# Netscale48HD_RFID_Reader_Writer.net
KiCad netlist of a schematic drawn in Altium Designer
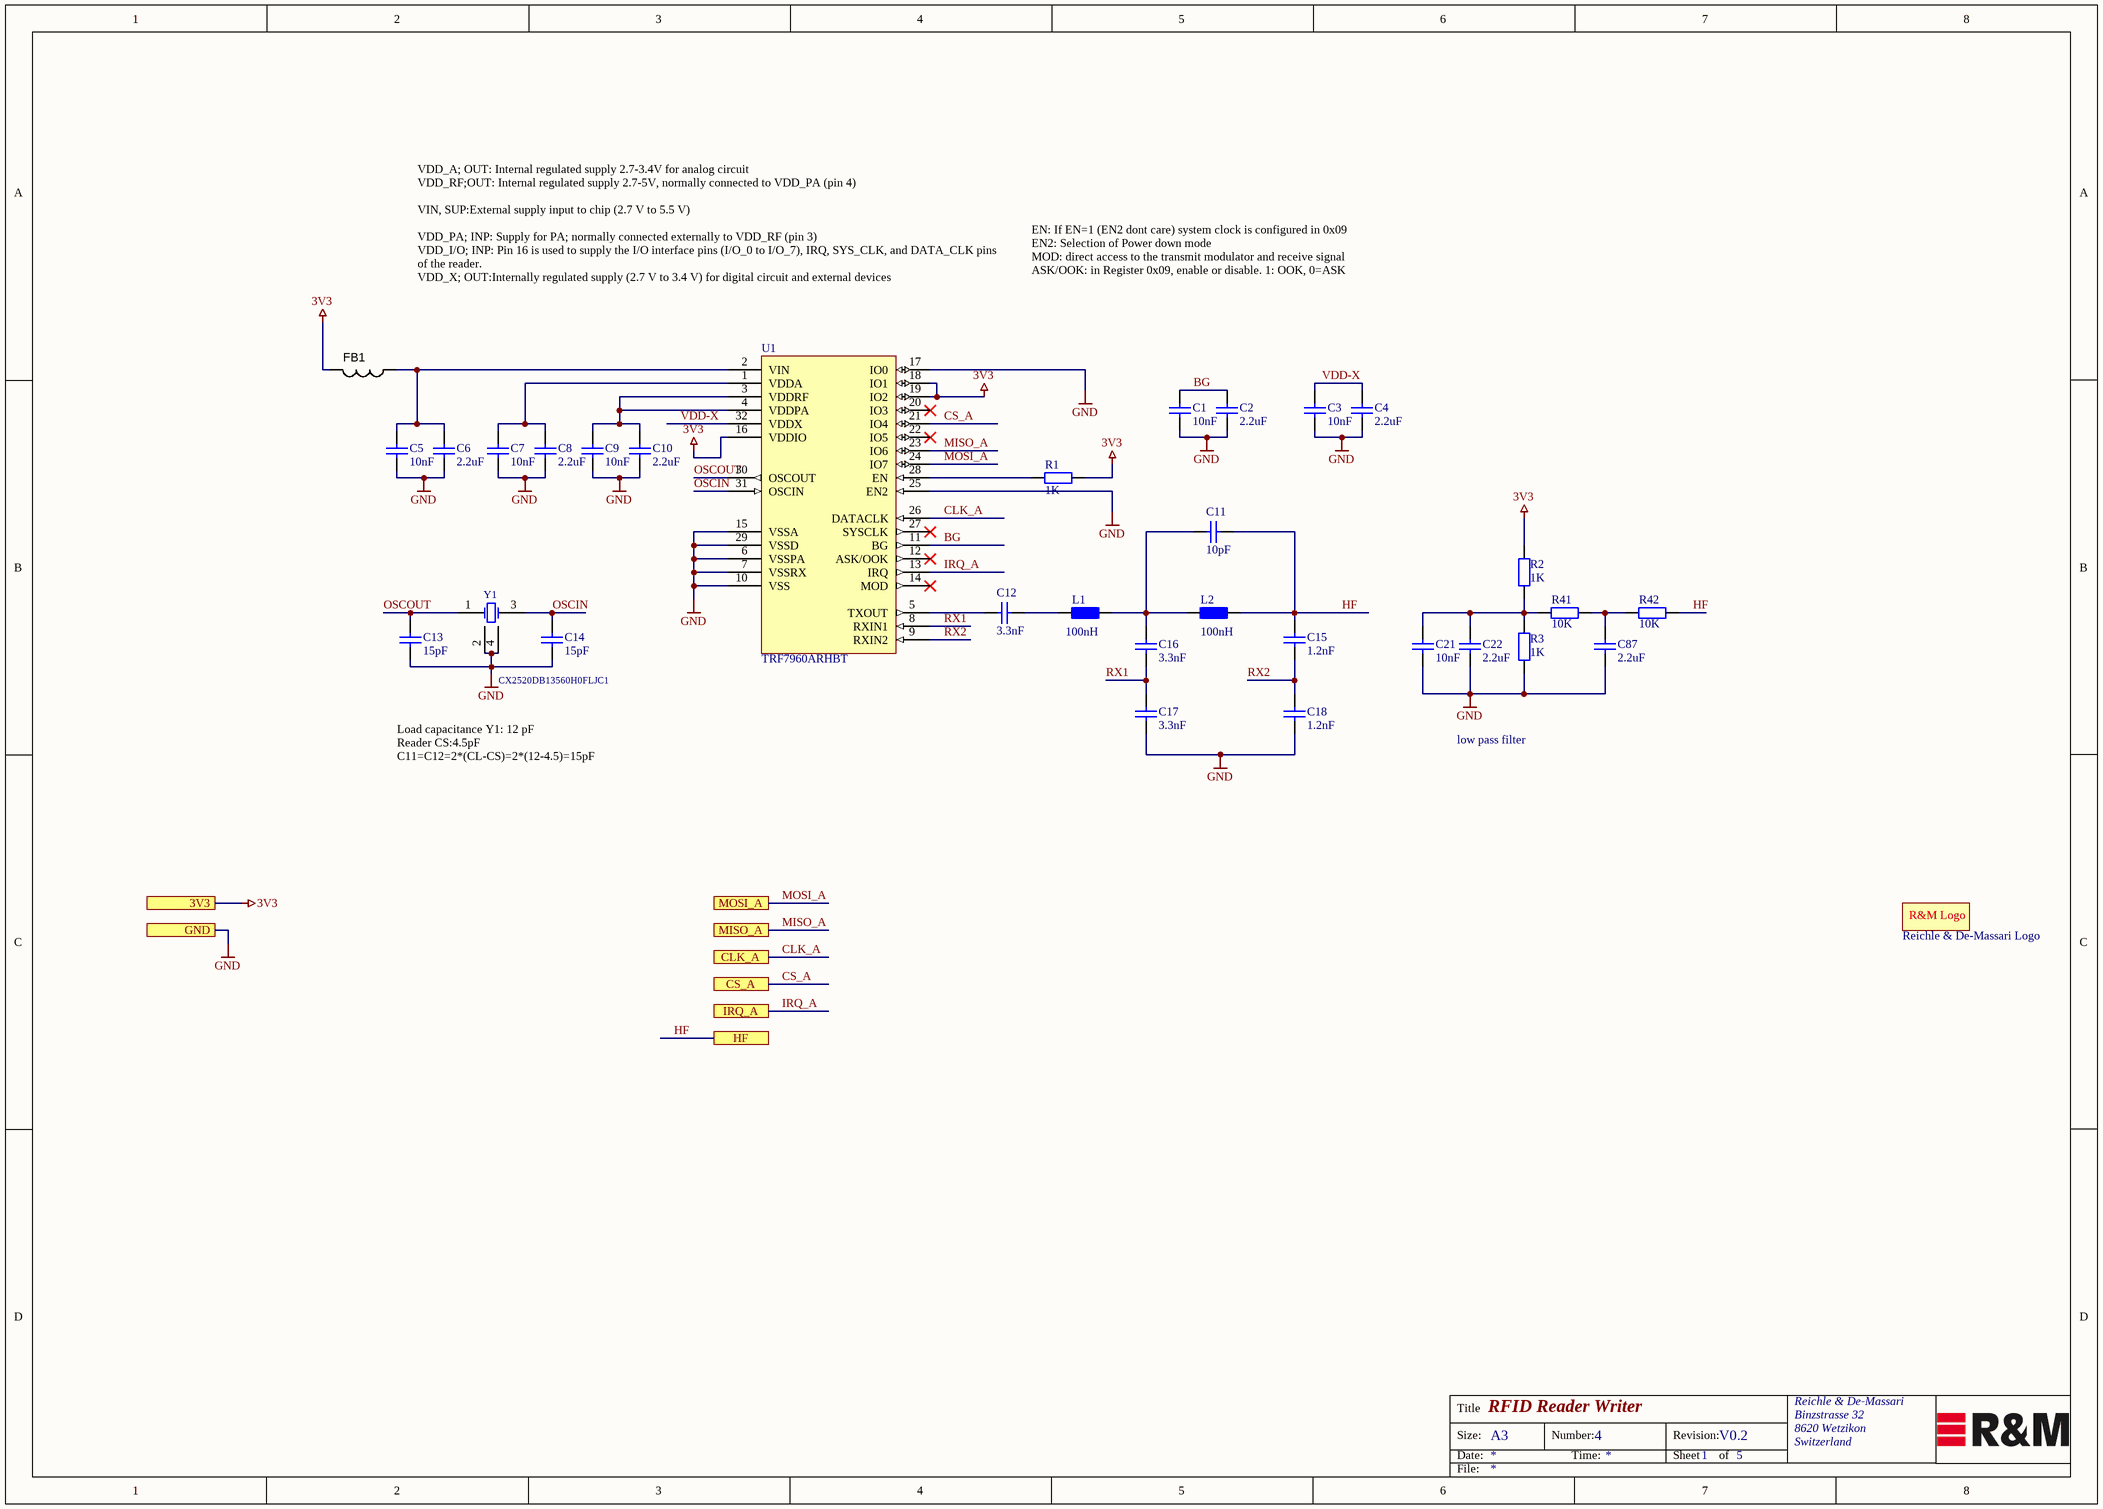
[diagram p0: Netscale48HD_RFID_Reader_Writer.SchDoc]

(export (version "E")
  (design (tool "Eeschema 10.0.6"))
  (components
    (comp (ref "*1")
      (value "Reichle & De-Massari Logo")
      (footprint "SYMBOL_R&M")
      (libsource (lib "RDM_ALT_SCH") (part "SYMBOL_R&M"))
    )
    (comp (ref "C1")
      (value "10nF")
      (footprint "Ceramic Capacitor 0402 EIA")
      (description "10000pF ±10% 50V Keramikkondensatoren X7R 0402 (1005 metrisch) CL05B103KB5NNNC")
      (fields (field (name "TOLERANCE") "±10%") (field (name "VOLTAGE") "50V"))
      (libsource (lib "RDM_ALT_SCH") (part "Cap_10nF_0402"))
    )
    (comp (ref "C2")
      (value "2.2uF")
      (footprint "Ceramic Capacitor 0402 EIA")
      (description "Multilayer Ceramic Capacitors MLCC - SMD/SMT 0402 2.2uF 6.3volts *Derate Voltage/Temp")
      (fields (field (name "TOLERANCE") "±20%") (field (name "VOLTAGE") "6.3V"))
      (libsource (lib "RDM_ALT_SCH") (part "Cap_2.2uF_0402_6.3V"))
    )
    (comp (ref "C3")
      (value "10nF")
      (footprint "Ceramic Capacitor 0402 EIA")
      (description "10000pF ±10% 50V Keramikkondensatoren X7R 0402 (1005 metrisch) CL05B103KB5NNNC")
      (fields (field (name "TOLERANCE") "±10%") (field (name "VOLTAGE") "50V"))
      (libsource (lib "RDM_ALT_SCH") (part "Cap_10nF_0402"))
    )
    (comp (ref "C4")
      (value "2.2uF")
      (footprint "Ceramic Capacitor 0402 EIA")
      (description "Multilayer Ceramic Capacitors MLCC - SMD/SMT 0402 2.2uF 6.3volts *Derate Voltage/Temp")
      (fields (field (name "TOLERANCE") "±20%") (field (name "VOLTAGE") "6.3V"))
      (libsource (lib "RDM_ALT_SCH") (part "Cap_2.2uF_0402_6.3V"))
    )
    (comp (ref "C5")
      (value "10nF")
      (footprint "Ceramic Capacitor 0402 EIA")
      (description "10000pF ±10% 50V Keramikkondensatoren X7R 0402 (1005 metrisch) CL05B103KB5NNNC")
      (fields (field (name "TOLERANCE") "±10%") (field (name "VOLTAGE") "50V"))
      (libsource (lib "RDM_ALT_SCH") (part "Cap_10nF_0402"))
    )
    (comp (ref "C6")
      (value "2.2uF")
      (footprint "Ceramic Capacitor 0402 EIA")
      (description "Multilayer Ceramic Capacitors MLCC - SMD/SMT 0402 2.2uF 6.3volts *Derate Voltage/Temp")
      (fields (field (name "TOLERANCE") "±20%") (field (name "VOLTAGE") "6.3V"))
      (libsource (lib "RDM_ALT_SCH") (part "Cap_2.2uF_0402_6.3V"))
    )
    (comp (ref "C7")
      (value "10nF")
      (footprint "Ceramic Capacitor 0402 EIA")
      (description "10000pF ±10% 50V Keramikkondensatoren X7R 0402 (1005 metrisch) CL05B103KB5NNNC")
      (fields (field (name "TOLERANCE") "±10%") (field (name "VOLTAGE") "50V"))
      (libsource (lib "RDM_ALT_SCH") (part "Cap_10nF_0402"))
    )
    (comp (ref "C8")
      (value "2.2uF")
      (footprint "Ceramic Capacitor 0402 EIA")
      (description "Multilayer Ceramic Capacitors MLCC - SMD/SMT 0402 2.2uF 6.3volts *Derate Voltage/Temp")
      (fields (field (name "TOLERANCE") "±20%") (field (name "VOLTAGE") "6.3V"))
      (libsource (lib "RDM_ALT_SCH") (part "Cap_2.2uF_0402_6.3V"))
    )
    (comp (ref "C9")
      (value "10nF")
      (footprint "Ceramic Capacitor 0402 EIA")
      (description "10000pF ±10% 50V Keramikkondensatoren X7R 0402 (1005 metrisch) CL05B103KB5NNNC")
      (fields (field (name "TOLERANCE") "±10%") (field (name "VOLTAGE") "50V"))
      (libsource (lib "RDM_ALT_SCH") (part "Cap_10nF_0402"))
    )
    (comp (ref "C10")
      (value "2.2uF")
      (footprint "Ceramic Capacitor 0402 EIA")
      (description "Multilayer Ceramic Capacitors MLCC - SMD/SMT 0402 2.2uF 6.3volts *Derate Voltage/Temp")
      (fields (field (name "TOLERANCE") "±20%") (field (name "VOLTAGE") "6.3V"))
      (libsource (lib "RDM_ALT_SCH") (part "Cap_2.2uF_0402_6.3V"))
    )
    (comp (ref "C11")
      (value "10pF")
      (footprint "Ceramic Capacitor 0402 EIA")
      (description "Multilayer Ceramic Capacitors MLCC - SMD/SMT 0402 10pF 50Volts C0G 1%")
      (fields (field (name "TOLERANCE") "1%") (field (name "VOLTAGE") "50VDC"))
      (libsource (lib "RDM_ALT_SCH") (part "Cap_10pF_0402"))
    )
    (comp (ref "C12")
      (value "3.3nF")
      (footprint "Ceramic Capacitor 0402 EIA")
      (description "Multilayer Ceramic Capacitors MLCC - SMD/SMT 0402 3300pF 50volts X7R 5%")
      (fields (field (name "TOLERANCE") "5%") (field (name "VOLTAGE") "50VDC"))
      (libsource (lib "RDM_ALT_SCH") (part "Cap_3.3nF_0402"))
    )
    (comp (ref "C13")
      (value "15pF")
      (footprint "Ceramic Capacitor 0402 EIA")
      (description "Multilayer Ceramic Capacitors MLCC - SMD/SMT 0402 15pF 50Volts C0G 5%")
      (fields (field (name "TOLERANCE") "±5%") (field (name "VOLTAGE") "50V"))
      (libsource (lib "RDM_ALT_SCH") (part "Cap_15pF_0402"))
    )
    (comp (ref "C14")
      (value "15pF")
      (footprint "Ceramic Capacitor 0402 EIA")
      (description "Multilayer Ceramic Capacitors MLCC - SMD/SMT 0402 15pF 50Volts C0G 5%")
      (fields (field (name "TOLERANCE") "±5%") (field (name "VOLTAGE") "50V"))
      (libsource (lib "RDM_ALT_SCH") (part "Cap_15pF_0402"))
    )
    (comp (ref "C15")
      (value "1.2nF")
      (footprint "Ceramic Capacitor 0402 EIA")
      (description "Multilayer Ceramic Capacitors MLCC - SMD/SMT 50V 1200pF C0G 0402 5%")
      (fields (field (name "TOLERANCE") "5%") (field (name "VOLTAGE") "50VDC"))
      (libsource (lib "RDM_ALT_SCH") (part "Cap_1.2nF_0402"))
    )
    (comp (ref "C16")
      (value "3.3nF")
      (footprint "Ceramic Capacitor 0402 EIA")
      (description "Multilayer Ceramic Capacitors MLCC - SMD/SMT 0402 3300pF 50volts X7R 5%")
      (fields (field (name "TOLERANCE") "5%") (field (name "VOLTAGE") "50VDC"))
      (libsource (lib "RDM_ALT_SCH") (part "Cap_3.3nF_0402"))
    )
    (comp (ref "C17")
      (value "3.3nF")
      (footprint "Ceramic Capacitor 0402 EIA")
      (description "Multilayer Ceramic Capacitors MLCC - SMD/SMT 0402 3300pF 50volts X7R 5%")
      (fields (field (name "TOLERANCE") "5%") (field (name "VOLTAGE") "50VDC"))
      (libsource (lib "RDM_ALT_SCH") (part "Cap_3.3nF_0402"))
    )
    (comp (ref "C18")
      (value "1.2nF")
      (footprint "Ceramic Capacitor 0402 EIA")
      (description "Multilayer Ceramic Capacitors MLCC - SMD/SMT 50V 1200pF C0G 0402 5%")
      (fields (field (name "TOLERANCE") "5%") (field (name "VOLTAGE") "50VDC"))
      (libsource (lib "RDM_ALT_SCH") (part "Cap_1.2nF_0402"))
    )
    (comp (ref "C21")
      (value "10nF")
      (footprint "Ceramic Capacitor 0402 EIA")
      (description "10000pF ±10% 50V Keramikkondensatoren X7R 0402 (1005 metrisch) CL05B103KB5NNNC")
      (fields (field (name "TOLERANCE") "±10%") (field (name "VOLTAGE") "50V"))
      (libsource (lib "RDM_ALT_SCH") (part "Cap_10nF_0402"))
    )
    (comp (ref "C22")
      (value "2.2uF")
      (footprint "Ceramic Capacitor 0402 EIA")
      (description "Multilayer Ceramic Capacitors MLCC - SMD/SMT 0402 2.2uF 6.3volts *Derate Voltage/Temp")
      (fields (field (name "TOLERANCE") "±20%") (field (name "VOLTAGE") "6.3V"))
      (libsource (lib "RDM_ALT_SCH") (part "Cap_2.2uF_0402_6.3V"))
    )
    (comp (ref "C87")
      (value "2.2uF")
      (footprint "Ceramic Capacitor 0402 EIA")
      (description "Multilayer Ceramic Capacitors MLCC - SMD/SMT 0402 2.2uF 6.3volts *Derate Voltage/Temp")
      (fields (field (name "TOLERANCE") "±20%") (field (name "VOLTAGE") "6.3V"))
      (libsource (lib "RDM_ALT_SCH") (part "Cap_2.2uF_0402_6.3V"))
    )
    (comp (ref "FB1")
      (value "BK1005HS102-T")
      (footprint "CAPC1005X55N")
      (description "FERRITE BEAD 1 KOHM 0402 1LN")
      (fields (field (name "MANUFACTURER") "Taiyo Yuden"))
      (libsource (lib "PBL - Inductors") (part "FERRITE_2K2-100MHz_0603"))
    )
    (comp (ref "L1")
      (value "100nH")
      (footprint "Inductor 0603 EIA")
      (description "100nH Unshielded Multilayer Inductor 300mA 100 mOhm Max 0603 (1608 Metric)")
      (fields (field (name "MANUFACTURER") "Taiyo Yuden") (field (name "Comment") "HK1608R10J-T"))
      (libsource (lib "altium-import") (part "root_0_706xx_R+M_InteliPhyII_KTI-00029-A.1_"))
    )
    (comp (ref "L2")
      (value "100nH")
      (footprint "Inductor 0603 EIA")
      (description "100nH Unshielded Multilayer Inductor 300mA 100 mOhm Max 0603 (1608 Metric)")
      (fields (field (name "MANUFACTURER") "Taiyo Yuden") (field (name "Comment") "HK1608R10J-T"))
      (libsource (lib "altium-import") (part "root_0_706xx_R+M_InteliPhyII_KTI-00029-A.1_"))
    )
    (comp (ref "R1")
      (value "1K")
      (footprint "RESC1005X40N")
      (description "RES SMD 1K OHM 1% 1/16W 0402")
      (fields (field (name "MANUFACTURER") "Yageo") (field (name "Comment") "RC0402FR-071KL"))
      (libsource (lib "RDM_Altium_Library") (part "PassResBas0201-00654-A.2"))
    )
    (comp (ref "R2")
      (value "1K")
      (footprint "RESC1005X40N")
      (description "RES SMD 1K OHM 1% 1/16W 0402")
      (fields (field (name "MANUFACTURER") "Yageo") (field (name "Comment") "RC0402FR-071KL"))
      (libsource (lib "NTB Vault") (part "PassResBas0201-00654-A.2"))
    )
    (comp (ref "R3")
      (value "1K")
      (footprint "RESC1005X40N")
      (description "RES SMD 1K OHM 1% 1/16W 0402")
      (fields (field (name "MANUFACTURER") "Yageo") (field (name "Comment") "RC0402FR-071KL"))
      (libsource (lib "NTB Vault") (part "PassResBas0201-00654-A.2"))
    )
    (comp (ref "R41")
      (value "10K")
      (footprint "Resistor 0402 EIA")
      (description "SMD 10K ohm 1% 50V General Purpose")
      (fields (field (name "TOLERANCE") "1%") (field (name "POWER") "63mW"))
      (libsource (lib "RDM_ALT_SCH") (part "Res_10K_0402"))
    )
    (comp (ref "R42")
      (value "10K")
      (footprint "Resistor 0402 EIA")
      (description "SMD 10K ohm 1% 50V General Purpose")
      (fields (field (name "TOLERANCE") "1%") (field (name "POWER") "63mW"))
      (libsource (lib "RDM_ALT_SCH") (part "Res_10K_0402"))
    )
    (comp (ref "U1")
      (value "TRF7960ARHBT")
      (footprint "TexasInstruments_32-VFQFN_32_R")
      (fields (field (name "MANUFACTURER") "Texas Instruments"))
      (libsource (lib "RDM_Altium_Library") (part "TexasInstruments_TRF7960ARHBT_32-VFQFN_32"))
    )
    (comp (ref "Y1")
      (value "CX2520DB13560H0FLJC1")
      (footprint "AVX/Kyocera_DFN4_4_RWH")
      (description "13.56MHz ±10ppm Crystal 12pF 150 Ohms 4-SMD, No Lead")
      (fields (field (name "MANUFACTURER") "Kyocera International Inc. Electronic Components"))
      (libsource (lib "RDM_Altium_Library") (part "CRYSTAL_4Pin_1_3_1"))
    )
  )
  (nets
    (net (code "1") (name "/BG") (class "Default")
      (node (ref "C1") (pin "2") (pinfunction "2_2") (pintype "passive"))
      (node (ref "C2") (pin "2") (pinfunction "2_2") (pintype "passive"))
      (node (ref "U1") (pin "11") (pinfunction "BG_11") (pintype "output"))
    )
    (net (code "2") (name "/CLK_A") (class "Default")
      (node (ref "U1") (pin "26") (pinfunction "DATACLK_26") (pintype "input"))
    )
    (net (code "3") (name "/CS_A") (class "Default")
      (node (ref "U1") (pin "21") (pinfunction "IO4_21") (pintype "bidirectional"))
    )
    (net (code "4") (name "/HF") (class "Default")
      (node (ref "C11") (pin "1") (pinfunction "1_1") (pintype "passive"))
      (node (ref "C15") (pin "2") (pinfunction "2_2") (pintype "passive"))
      (node (ref "L2") (pin "2") (pinfunction "2_2") (pintype "passive"))
      (node (ref "R42") (pin "2") (pinfunction "2_2") (pintype "passive"))
    )
    (net (code "5") (name "/IRQ_A") (class "Default")
      (node (ref "U1") (pin "13") (pinfunction "IRQ_13") (pintype "output"))
    )
    (net (code "6") (name "/MISO_A") (class "Default")
      (node (ref "U1") (pin "23") (pinfunction "IO6_23") (pintype "bidirectional"))
    )
    (net (code "7") (name "/MOSI_A") (class "Default")
      (node (ref "U1") (pin "24") (pinfunction "IO7_24") (pintype "bidirectional"))
    )
    (net (code "8") (name "/OSCIN") (class "Default")
      (node (ref "C14") (pin "2") (pinfunction "2_2") (pintype "passive"))
      (node (ref "U1") (pin "31") (pinfunction "OSCIN_31") (pintype "input"))
      (node (ref "Y1") (pin "3") (pinfunction "OSC2_3") (pintype "passive"))
    )
    (net (code "9") (name "/OSCOUT") (class "Default")
      (node (ref "C13") (pin "2") (pinfunction "2_2") (pintype "passive"))
      (node (ref "U1") (pin "30") (pinfunction "OSCOUT_30") (pintype "output"))
      (node (ref "Y1") (pin "1") (pinfunction "OSC1_1") (pintype "passive"))
    )
    (net (code "10") (name "/RX1") (class "Default")
      (node (ref "C16") (pin "1") (pinfunction "1_1") (pintype "passive"))
      (node (ref "C17") (pin "2") (pinfunction "2_2") (pintype "passive"))
      (node (ref "U1") (pin "8") (pinfunction "RXIN1_8") (pintype "input"))
    )
    (net (code "11") (name "/RX2") (class "Default")
      (node (ref "C15") (pin "1") (pinfunction "1_1") (pintype "passive"))
      (node (ref "C18") (pin "2") (pinfunction "2_2") (pintype "passive"))
      (node (ref "U1") (pin "9") (pinfunction "RXIN2_9") (pintype "input"))
    )
    (net (code "12") (name "/VDD-X") (class "Default")
      (node (ref "C3") (pin "2") (pinfunction "2_2") (pintype "passive"))
      (node (ref "C4") (pin "2") (pinfunction "2_2") (pintype "passive"))
      (node (ref "U1") (pin "32") (pinfunction "VDDX_32") (pintype "power_in"))
    )
    (net (code "13") (name "3V3") (class "Default")
      (node (ref "FB1") (pin "2") (pinfunction "2_2") (pintype "passive"))
      (node (ref "R1") (pin "1") (pinfunction "1_1") (pintype "passive"))
      (node (ref "R2") (pin "1") (pinfunction "1_1") (pintype "passive"))
      (node (ref "U1") (pin "16") (pinfunction "VDDIO_16") (pintype "power_in"))
      (node (ref "U1") (pin "18") (pinfunction "IO1_18") (pintype "bidirectional"))
      (node (ref "U1") (pin "19") (pinfunction "IO2_19") (pintype "bidirectional"))
    )
    (net (code "14") (name "GND") (class "Default")
      (node (ref "C1") (pin "1") (pinfunction "1_1") (pintype "passive"))
      (node (ref "C10") (pin "1") (pinfunction "1_1") (pintype "passive"))
      (node (ref "C13") (pin "1") (pinfunction "1_1") (pintype "passive"))
      (node (ref "C14") (pin "1") (pinfunction "1_1") (pintype "passive"))
      (node (ref "C17") (pin "1") (pinfunction "1_1") (pintype "passive"))
      (node (ref "C18") (pin "1") (pinfunction "1_1") (pintype "passive"))
      (node (ref "C2") (pin "1") (pinfunction "1_1") (pintype "passive"))
      (node (ref "C21") (pin "1") (pinfunction "1_1") (pintype "passive"))
      (node (ref "C22") (pin "1") (pinfunction "1_1") (pintype "passive"))
      (node (ref "C3") (pin "1") (pinfunction "1_1") (pintype "passive"))
      (node (ref "C4") (pin "1") (pinfunction "1_1") (pintype "passive"))
      (node (ref "C5") (pin "1") (pinfunction "1_1") (pintype "passive"))
      (node (ref "C6") (pin "1") (pinfunction "1_1") (pintype "passive"))
      (node (ref "C7") (pin "1") (pinfunction "1_1") (pintype "passive"))
      (node (ref "C8") (pin "1") (pinfunction "1_1") (pintype "passive"))
      (node (ref "C87") (pin "1") (pinfunction "1_1") (pintype "passive"))
      (node (ref "C9") (pin "1") (pinfunction "1_1") (pintype "passive"))
      (node (ref "R3") (pin "2") (pinfunction "2_2") (pintype "passive"))
      (node (ref "U1") (pin "10") (pinfunction "VSS_10") (pintype "passive"))
      (node (ref "U1") (pin "15") (pinfunction "VSSA_15") (pintype "passive"))
      (node (ref "U1") (pin "17") (pinfunction "IO0_17") (pintype "bidirectional"))
      (node (ref "U1") (pin "25") (pinfunction "EN2_25") (pintype "input"))
      (node (ref "U1") (pin "29") (pinfunction "VSSD_29") (pintype "passive"))
      (node (ref "U1") (pin "6") (pinfunction "VSSPA_6") (pintype "passive"))
      (node (ref "U1") (pin "7") (pinfunction "VSSRX_7") (pintype "passive"))
      (node (ref "Y1") (pin "2") (pinfunction "OSC2_2") (pintype "passive"))
      (node (ref "Y1") (pin "4") (pinfunction "OSC3_4") (pintype "passive"))
    )
    (net (code "15") (name "Net-(C11-Pad2)") (class "Default")
      (node (ref "C11") (pin "2") (pinfunction "2_2") (pintype "passive"))
      (node (ref "C16") (pin "2") (pinfunction "2_2") (pintype "passive"))
      (node (ref "L1") (pin "2") (pinfunction "2_2") (pintype "passive"))
      (node (ref "L2") (pin "1") (pinfunction "1_1") (pintype "passive"))
    )
    (net (code "16") (name "Net-(C12-Pad1)") (class "Default")
      (node (ref "C12") (pin "1") (pinfunction "1_1") (pintype "passive"))
      (node (ref "L1") (pin "1") (pinfunction "1_1") (pintype "passive"))
    )
    (net (code "17") (name "Net-(C21-Pad2)") (class "Default")
      (node (ref "C21") (pin "2") (pinfunction "2_2") (pintype "passive"))
      (node (ref "C22") (pin "2") (pinfunction "2_2") (pintype "passive"))
      (node (ref "R2") (pin "2") (pinfunction "2_2") (pintype "passive"))
      (node (ref "R3") (pin "1") (pinfunction "1_1") (pintype "passive"))
      (node (ref "R41") (pin "1") (pinfunction "1_1") (pintype "passive"))
    )
    (net (code "18") (name "Net-(C87-Pad2)") (class "Default")
      (node (ref "C87") (pin "2") (pinfunction "2_2") (pintype "passive"))
      (node (ref "R41") (pin "2") (pinfunction "2_2") (pintype "passive"))
      (node (ref "R42") (pin "1") (pinfunction "1_1") (pintype "passive"))
    )
    (net (code "19") (name "Net-(U1-EN)") (class "Default")
      (node (ref "R1") (pin "2") (pinfunction "2_2") (pintype "passive"))
      (node (ref "U1") (pin "28") (pinfunction "EN_28") (pintype "input"))
    )
    (net (code "20") (name "Net-(U1-TXOUT)") (class "Default")
      (node (ref "C12") (pin "2") (pinfunction "2_2") (pintype "passive"))
      (node (ref "U1") (pin "5") (pinfunction "TXOUT_5") (pintype "output"))
    )
    (net (code "21") (name "Net-(U1-VDDA)") (class "Default")
      (node (ref "C7") (pin "2") (pinfunction "2_2") (pintype "passive"))
      (node (ref "C8") (pin "2") (pinfunction "2_2") (pintype "passive"))
      (node (ref "U1") (pin "1") (pinfunction "VDDA_1") (pintype "power_in"))
    )
    (net (code "22") (name "Net-(U1-VDDPA)") (class "Default")
      (node (ref "C10") (pin "2") (pinfunction "2_2") (pintype "passive"))
      (node (ref "C9") (pin "2") (pinfunction "2_2") (pintype "passive"))
      (node (ref "U1") (pin "3") (pinfunction "VDDRF_3") (pintype "power_in"))
      (node (ref "U1") (pin "4") (pinfunction "VDDPA_4") (pintype "power_in"))
    )
    (net (code "23") (name "Net-(U1-VIN)") (class "Default")
      (node (ref "C5") (pin "2") (pinfunction "2_2") (pintype "passive"))
      (node (ref "C6") (pin "2") (pinfunction "2_2") (pintype "passive"))
      (node (ref "FB1") (pin "1") (pinfunction "1_1") (pintype "passive"))
      (node (ref "U1") (pin "2") (pinfunction "VIN_2") (pintype "power_in"))
    )
    (net (code "24") (name "unconnected-(U1-ASK{slash}OOK-Pad12)") (class "Default")
      (node (ref "U1") (pin "12") (pinfunction "ASK/OOK_12") (pintype "output+no_connect"))
    )
    (net (code "25") (name "unconnected-(U1-IO3-Pad20)") (class "Default")
      (node (ref "U1") (pin "20") (pinfunction "IO3_20") (pintype "bidirectional+no_connect"))
    )
    (net (code "26") (name "unconnected-(U1-IO5-Pad22)") (class "Default")
      (node (ref "U1") (pin "22") (pinfunction "IO5_22") (pintype "bidirectional+no_connect"))
    )
    (net (code "27") (name "unconnected-(U1-MOD-Pad14)") (class "Default")
      (node (ref "U1") (pin "14") (pinfunction "MOD_14") (pintype "output+no_connect"))
    )
    (net (code "28") (name "unconnected-(U1-SYSCLK-Pad27)") (class "Default")
      (node (ref "U1") (pin "27") (pinfunction "SYSCLK_27") (pintype "output+no_connect"))
    )
  )
)
